# RPi-Display_v10.net
KiCad netlist of a schematic drawn in EAGLE
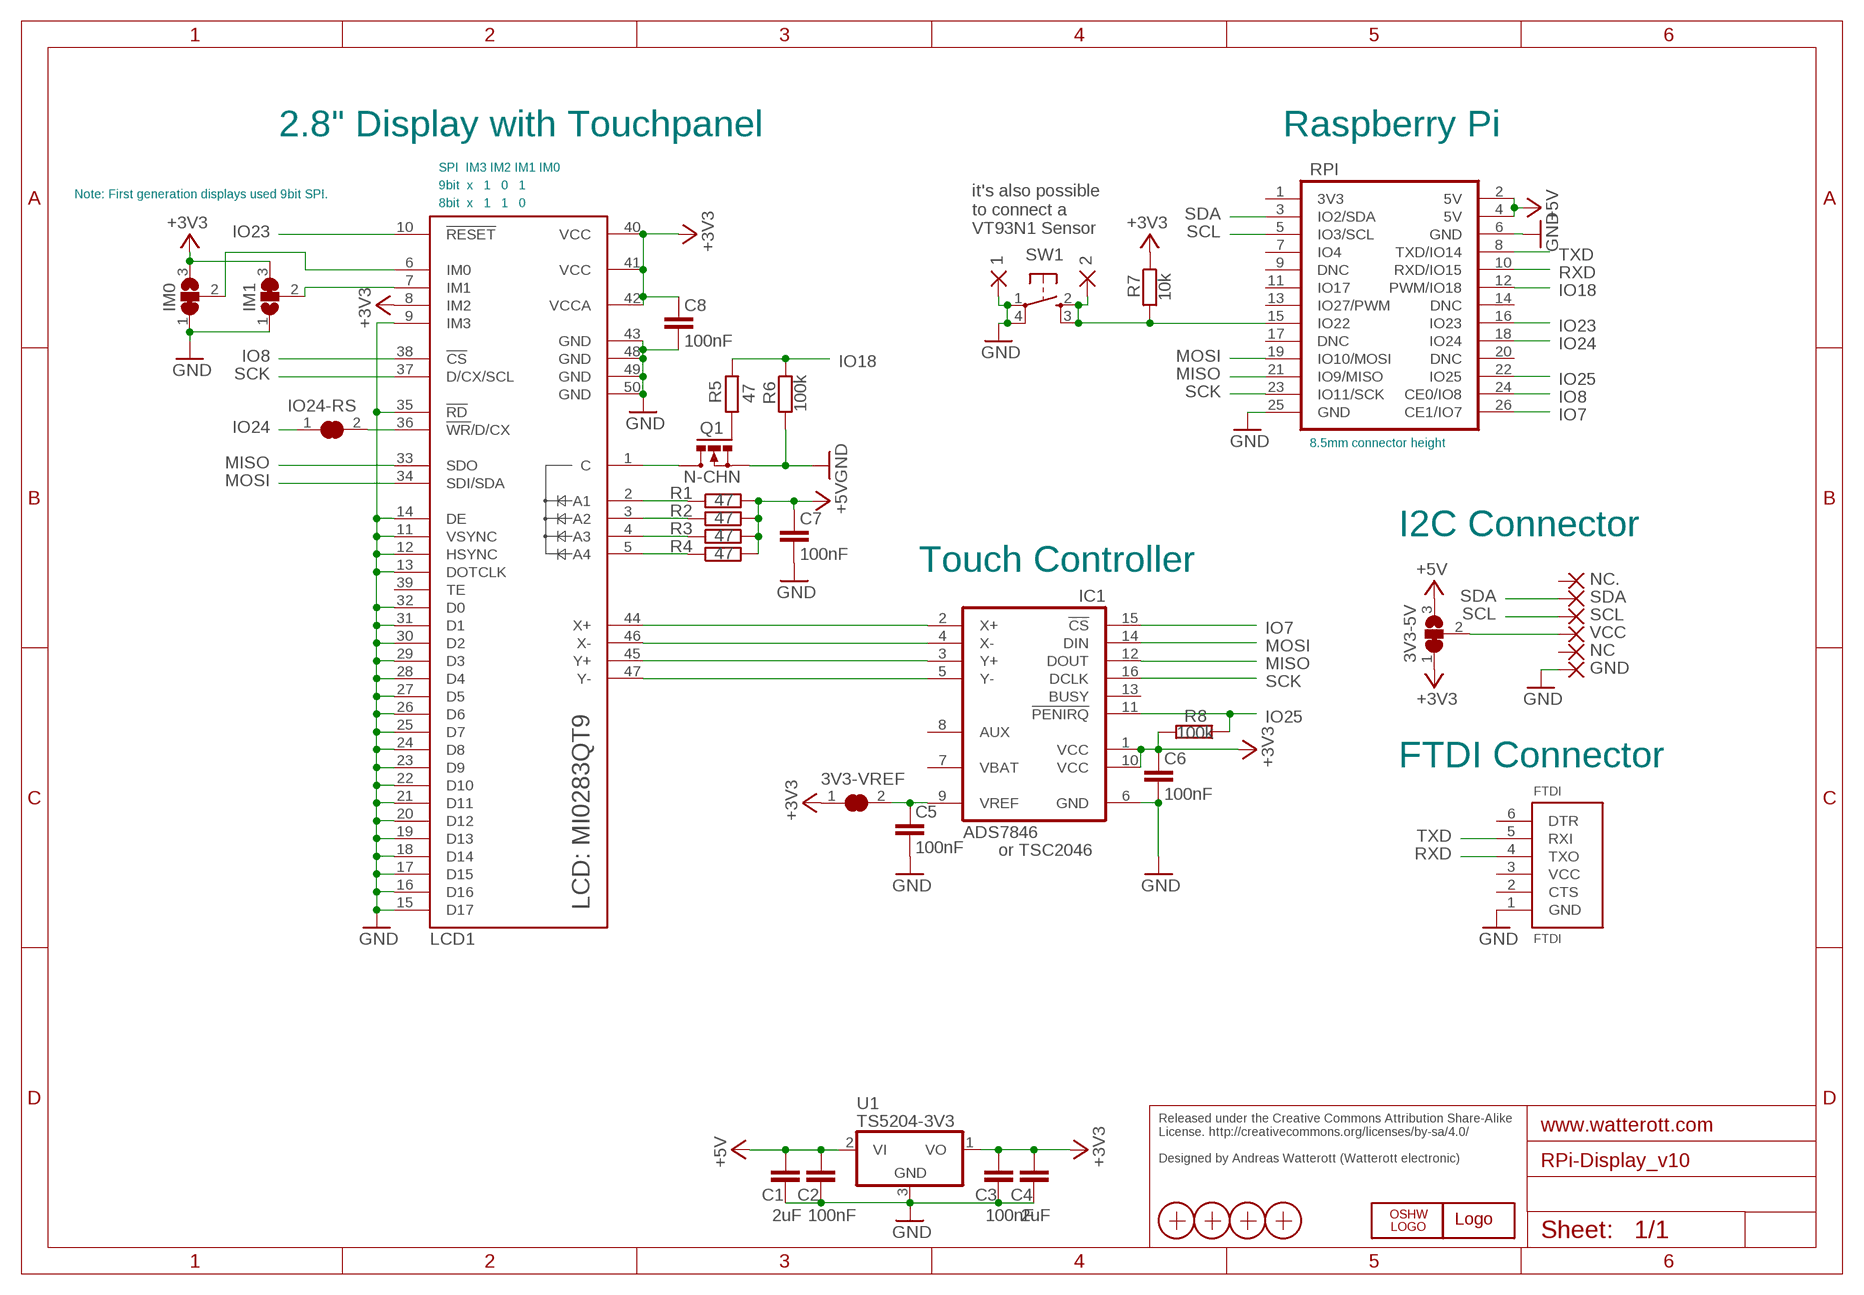
[diagram p0: schematic, sheet 1]

(export (version "E")
  (design (tool "Eeschema 10.0.6"))
  (components
    (comp (ref "1")
      (value "WIREPADSMD1,27-254")
      (footprint "eagle-import:SMD1,27-2,54")
      (libsource (lib "eagle-import") (part "WIREPADSMD1,27-254"))
    )
    (comp (ref "2")
      (value "WIREPADSMD1,27-254")
      (footprint "eagle-import:SMD1,27-2,54")
      (libsource (lib "eagle-import") (part "WIREPADSMD1,27-254"))
    )
    (comp (ref "3V3-5V")
      (value "SJ2W")
      (footprint "eagle-import:SJ_2")
      (libsource (lib "eagle-import") (part "SJ2W"))
    )
    (comp (ref "3V3-VREF")
      (value "SJ")
      (footprint "eagle-import:SJ")
      (libsource (lib "eagle-import") (part "SJ"))
    )
    (comp (ref "C1")
      (value "2uF")
      (footprint "eagle-import:C0603")
      (libsource (lib "eagle-import") (part "C-EUC0603"))
    )
    (comp (ref "C2")
      (value "100nF")
      (footprint "eagle-import:C0603")
      (libsource (lib "eagle-import") (part "C-EUC0603"))
    )
    (comp (ref "C3")
      (value "100nF")
      (footprint "eagle-import:C0603")
      (libsource (lib "eagle-import") (part "C-EUC0603"))
    )
    (comp (ref "C4")
      (value "2uF")
      (footprint "eagle-import:C0603")
      (libsource (lib "eagle-import") (part "C-EUC0603"))
    )
    (comp (ref "C5")
      (value "100nF")
      (footprint "eagle-import:C0603")
      (libsource (lib "eagle-import") (part "C-EUC0603"))
    )
    (comp (ref "C6")
      (value "100nF")
      (footprint "eagle-import:C0603")
      (libsource (lib "eagle-import") (part "C-EUC0603"))
    )
    (comp (ref "C7")
      (value "100nF")
      (footprint "eagle-import:C0603")
      (libsource (lib "eagle-import") (part "C-EUC0603"))
    )
    (comp (ref "C8")
      (value "100nF")
      (footprint "eagle-import:C0603")
      (libsource (lib "eagle-import") (part "C-EUC0603"))
    )
    (comp (ref "FTDI")
      (value "FTDI")
      (footprint "eagle-import:FTDI")
      (libsource (lib "eagle-import") (part "FTDI"))
    )
    (comp (ref "GND")
      (value "WIREPADSMD1,27-254")
      (footprint "eagle-import:SMD1,27-2,54")
      (libsource (lib "eagle-import") (part "WIREPADSMD1,27-254"))
    )
    (comp (ref "IC1")
      (value "ADS7846")
      (footprint "eagle-import:SSOP16")
      (libsource (lib "eagle-import") (part "ADS7846"))
    )
    (comp (ref "IM0")
      (value "SJ2W")
      (footprint "eagle-import:SJ_2")
      (libsource (lib "eagle-import") (part "SJ2W"))
    )
    (comp (ref "IM1")
      (value "SJ2W")
      (footprint "eagle-import:SJ_2")
      (libsource (lib "eagle-import") (part "SJ2W"))
    )
    (comp (ref "IO24-RS")
      (value "SJ")
      (footprint "eagle-import:SJ")
      (libsource (lib "eagle-import") (part "SJ"))
    )
    (comp (ref "LCD1")
      (value "MI0283QT9")
      (footprint "eagle-import:MI0283QT9")
      (libsource (lib "eagle-import") (part "MI0283QT9"))
    )
    (comp (ref "LOGO1")
      (value "OSHW_LOGO_6MILX0150-NT")
      (footprint "eagle-import:OSHW_6X150_NOTEXT")
      (libsource (lib "eagle-import") (part "OSHW_LOGO_6MILX0150-NT"))
    )
    (comp (ref "NC")
      (value "WIREPADSMD1,27-254")
      (footprint "eagle-import:SMD1,27-2,54")
      (libsource (lib "eagle-import") (part "WIREPADSMD1,27-254"))
    )
    (comp (ref "NC.")
      (value "WIREPADSMD1,27-254")
      (footprint "eagle-import:SMD1,27-2,54")
      (libsource (lib "eagle-import") (part "WIREPADSMD1,27-254"))
    )
    (comp (ref "Q1")
      (value "N-CHN")
      (footprint "eagle-import:MICRO3")
      (libsource (lib "eagle-import") (part "IRLML2502"))
    )
    (comp (ref "R1")
      (value "47")
      (footprint "eagle-import:R0603")
      (libsource (lib "eagle-import") (part "R-EU_R0603"))
    )
    (comp (ref "R2")
      (value "47")
      (footprint "eagle-import:R0603")
      (libsource (lib "eagle-import") (part "R-EU_R0603"))
    )
    (comp (ref "R3")
      (value "47")
      (footprint "eagle-import:R0603")
      (libsource (lib "eagle-import") (part "R-EU_R0603"))
    )
    (comp (ref "R4")
      (value "47")
      (footprint "eagle-import:R0603")
      (libsource (lib "eagle-import") (part "R-EU_R0603"))
    )
    (comp (ref "R5")
      (value "47")
      (footprint "eagle-import:R0603")
      (libsource (lib "eagle-import") (part "R-EU_R0603"))
    )
    (comp (ref "R6")
      (value "100k")
      (footprint "eagle-import:R0603")
      (libsource (lib "eagle-import") (part "R-EU_R0603"))
    )
    (comp (ref "R7")
      (value "10k")
      (footprint "eagle-import:R0603")
      (libsource (lib "eagle-import") (part "R-EU_R0603"))
    )
    (comp (ref "R8")
      (value "100k")
      (footprint "eagle-import:R0603")
      (libsource (lib "eagle-import") (part "R-EU_R0603"))
    )
    (comp (ref "RPI")
      (value "RPI")
      (footprint "eagle-import:RPI")
      (libsource (lib "eagle-import") (part "RPI"))
    )
    (comp (ref "SCL")
      (value "WIREPADSMD1,27-254")
      (footprint "eagle-import:SMD1,27-2,54")
      (libsource (lib "eagle-import") (part "WIREPADSMD1,27-254"))
    )
    (comp (ref "SDA")
      (value "WIREPADSMD1,27-254")
      (footprint "eagle-import:SMD1,27-2,54")
      (libsource (lib "eagle-import") (part "WIREPADSMD1,27-254"))
    )
    (comp (ref "SW1")
      (value "SW4S")
      (footprint "eagle-import:SW_SMD4")
      (libsource (lib "eagle-import") (part "SW4S"))
    )
    (comp (ref "U$1")
      (value "WE-LOGO")
      (footprint "eagle-import:WE-LOGO")
      (libsource (lib "eagle-import") (part "WE-LOGOPLACE"))
    )
    (comp (ref "U1")
      (value "TS5204-3V3")
      (footprint "eagle-import:SOT23")
      (libsource (lib "eagle-import") (part "TS5204"))
    )
    (comp (ref "VCC")
      (value "WIREPADSMD1,27-254")
      (footprint "eagle-import:SMD1,27-2,54")
      (libsource (lib "eagle-import") (part "WIREPADSMD1,27-254"))
    )
    (comp (ref "X1")
      (value "PASSER")
      (footprint "eagle-import:PASSER")
      (libsource (lib "eagle-import") (part "PASSER"))
    )
    (comp (ref "X2")
      (value "PASSER")
      (footprint "eagle-import:PASSER")
      (libsource (lib "eagle-import") (part "PASSER"))
    )
    (comp (ref "X3")
      (value "PASSER")
      (footprint "eagle-import:PASSER")
      (libsource (lib "eagle-import") (part "PASSER"))
    )
    (comp (ref "X4")
      (value "PASSER")
      (footprint "eagle-import:PASSER")
      (libsource (lib "eagle-import") (part "PASSER"))
    )
  )
  (nets
    (net (code "1") (name "+3V3") (class "Default")
      (node (ref "3V3-5V") (pin "1") (pinfunction "1_1") (pintype "passive"))
      (node (ref "3V3-VREF") (pin "1") (pinfunction "1_1") (pintype "passive"))
      (node (ref "C3") (pin "1") (pinfunction "1_1") (pintype "passive"))
      (node (ref "C4") (pin "1") (pinfunction "1_1") (pintype "passive"))
      (node (ref "C6") (pin "1") (pinfunction "1_1") (pintype "passive"))
      (node (ref "C8") (pin "1") (pinfunction "1_1") (pintype "passive"))
      (node (ref "IC1") (pin "1") (pinfunction "VCC_1") (pintype "power_in"))
      (node (ref "IC1") (pin "10") (pinfunction "VCC_10") (pintype "power_in"))
      (node (ref "IM0") (pin "3") (pinfunction "3_3") (pintype "passive"))
      (node (ref "IM1") (pin "3") (pinfunction "3_3") (pintype "passive"))
      (node (ref "LCD1") (pin "40") (pinfunction "VCC_40") (pintype "power_in"))
      (node (ref "LCD1") (pin "41") (pinfunction "VCC_41") (pintype "power_in"))
      (node (ref "LCD1") (pin "42") (pinfunction "VCCA_42") (pintype "power_in"))
      (node (ref "LCD1") (pin "8") (pinfunction "IM2_8") (pintype "input"))
      (node (ref "R7") (pin "1") (pinfunction "1_1") (pintype "passive"))
      (node (ref "R8") (pin "2") (pinfunction "2_2") (pintype "passive"))
      (node (ref "U1") (pin "1") (pinfunction "VO_1") (pintype "passive"))
    )
    (net (code "2") (name "+5V") (class "Default")
      (node (ref "3V3-5V") (pin "3") (pinfunction "3_3") (pintype "passive"))
      (node (ref "C1") (pin "1") (pinfunction "1_1") (pintype "passive"))
      (node (ref "C2") (pin "1") (pinfunction "1_1") (pintype "passive"))
      (node (ref "C7") (pin "1") (pinfunction "1_1") (pintype "passive"))
      (node (ref "R1") (pin "2") (pinfunction "2_2") (pintype "passive"))
      (node (ref "R2") (pin "2") (pinfunction "2_2") (pintype "passive"))
      (node (ref "R3") (pin "2") (pinfunction "2_2") (pintype "passive"))
      (node (ref "R4") (pin "2") (pinfunction "2_2") (pintype "passive"))
      (node (ref "RPI") (pin "2") (pinfunction "5V_2") (pintype "passive"))
      (node (ref "RPI") (pin "4") (pinfunction "5V_4") (pintype "passive"))
      (node (ref "U1") (pin "2") (pinfunction "VI_2") (pintype "input"))
    )
    (net (code "3") (name "/IO7") (class "Default")
      (node (ref "IC1") (pin "15") (pinfunction "~{CS}_15") (pintype "input"))
      (node (ref "RPI") (pin "26") (pinfunction "CE1/IO7_26") (pintype "passive"))
    )
    (net (code "4") (name "/IO8") (class "Default")
      (node (ref "LCD1") (pin "38") (pinfunction "~{CS}_38") (pintype "input"))
      (node (ref "RPI") (pin "24") (pinfunction "CE0/IO8_24") (pintype "passive"))
    )
    (net (code "5") (name "/IO18") (class "Default")
      (node (ref "R5") (pin "2") (pinfunction "2_2") (pintype "passive"))
      (node (ref "R6") (pin "1") (pinfunction "1_1") (pintype "passive"))
      (node (ref "RPI") (pin "12") (pinfunction "PWM/IO18_12") (pintype "passive"))
    )
    (net (code "6") (name "/IO23") (class "Default")
      (node (ref "LCD1") (pin "10") (pinfunction "~{RESET}_10") (pintype "input"))
      (node (ref "RPI") (pin "16") (pinfunction "IO23_16") (pintype "passive"))
    )
    (net (code "7") (name "/IO24") (class "Default")
      (node (ref "IO24-RS") (pin "1") (pinfunction "1_1") (pintype "passive"))
      (node (ref "RPI") (pin "18") (pinfunction "IO24_18") (pintype "passive"))
    )
    (net (code "8") (name "/IO25") (class "Default")
      (node (ref "IC1") (pin "11") (pinfunction "~{PENIRQ}_11") (pintype "output"))
      (node (ref "R8") (pin "1") (pinfunction "1_1") (pintype "passive"))
      (node (ref "RPI") (pin "22") (pinfunction "IO25_22") (pintype "passive"))
    )
    (net (code "9") (name "/MISO") (class "Default")
      (node (ref "IC1") (pin "12") (pinfunction "DOUT_12") (pintype "input"))
      (node (ref "LCD1") (pin "33") (pinfunction "SDO_33") (pintype "output"))
      (node (ref "RPI") (pin "21") (pinfunction "IO9/MISO_21") (pintype "passive"))
    )
    (net (code "10") (name "/MOSI") (class "Default")
      (node (ref "IC1") (pin "14") (pinfunction "DIN_14") (pintype "input"))
      (node (ref "LCD1") (pin "34") (pinfunction "SDI/SDA_34") (pintype "input"))
      (node (ref "RPI") (pin "19") (pinfunction "IO10/MOSI_19") (pintype "passive"))
    )
    (net (code "11") (name "/RXD") (class "Default")
      (node (ref "FTDI") (pin "4") (pinfunction "TXO_4") (pintype "bidirectional"))
      (node (ref "RPI") (pin "10") (pinfunction "RXD/IO15_10") (pintype "passive"))
    )
    (net (code "12") (name "/SCK") (class "Default")
      (node (ref "IC1") (pin "16") (pinfunction "DCLK_16") (pintype "output"))
      (node (ref "LCD1") (pin "37") (pinfunction "D/CX/SCL_37") (pintype "input"))
      (node (ref "RPI") (pin "23") (pinfunction "IO11/SCK_23") (pintype "passive"))
    )
    (net (code "13") (name "/SCL") (class "Default")
      (node (ref "RPI") (pin "5") (pinfunction "IO3/SCL_5") (pintype "passive"))
      (node (ref "SCL") (pin "1") (pinfunction "P_1") (pintype "passive"))
    )
    (net (code "14") (name "/SDA") (class "Default")
      (node (ref "RPI") (pin "3") (pinfunction "IO2/SDA_3") (pintype "passive"))
      (node (ref "SDA") (pin "1") (pinfunction "P_1") (pintype "passive"))
    )
    (net (code "15") (name "/TXD") (class "Default")
      (node (ref "FTDI") (pin "5") (pinfunction "RXI_5") (pintype "bidirectional"))
      (node (ref "RPI") (pin "8") (pinfunction "TXD/IO14_8") (pintype "passive"))
    )
    (net (code "16") (name "GND") (class "Default")
      (node (ref "1") (pin "1") (pinfunction "P_1") (pintype "passive"))
      (node (ref "C1") (pin "2") (pinfunction "2_2") (pintype "passive"))
      (node (ref "C2") (pin "2") (pinfunction "2_2") (pintype "passive"))
      (node (ref "C3") (pin "2") (pinfunction "2_2") (pintype "passive"))
      (node (ref "C4") (pin "2") (pinfunction "2_2") (pintype "passive"))
      (node (ref "C5") (pin "2") (pinfunction "2_2") (pintype "passive"))
      (node (ref "C6") (pin "2") (pinfunction "2_2") (pintype "passive"))
      (node (ref "C7") (pin "2") (pinfunction "2_2") (pintype "passive"))
      (node (ref "C8") (pin "2") (pinfunction "2_2") (pintype "passive"))
      (node (ref "FTDI") (pin "1") (pinfunction "GND_1") (pintype "bidirectional"))
      (node (ref "GND") (pin "1") (pinfunction "P_1") (pintype "passive"))
      (node (ref "IC1") (pin "6") (pinfunction "GND_6") (pintype "power_in"))
      (node (ref "IM0") (pin "1") (pinfunction "1_1") (pintype "passive"))
      (node (ref "IM1") (pin "1") (pinfunction "1_1") (pintype "passive"))
      (node (ref "LCD1") (pin "11") (pinfunction "VSYNC_11") (pintype "input"))
      (node (ref "LCD1") (pin "12") (pinfunction "HSYNC_12") (pintype "input"))
      (node (ref "LCD1") (pin "13") (pinfunction "DOTCLK_13") (pintype "input"))
      (node (ref "LCD1") (pin "14") (pinfunction "DE_14") (pintype "input"))
      (node (ref "LCD1") (pin "15") (pinfunction "D17_15") (pintype "input"))
      (node (ref "LCD1") (pin "16") (pinfunction "D16_16") (pintype "input"))
      (node (ref "LCD1") (pin "17") (pinfunction "D15_17") (pintype "input"))
      (node (ref "LCD1") (pin "18") (pinfunction "D14_18") (pintype "input"))
      (node (ref "LCD1") (pin "19") (pinfunction "D13_19") (pintype "input"))
      (node (ref "LCD1") (pin "20") (pinfunction "D12_20") (pintype "input"))
      (node (ref "LCD1") (pin "21") (pinfunction "D11_21") (pintype "input"))
      (node (ref "LCD1") (pin "22") (pinfunction "D10_22") (pintype "input"))
      (node (ref "LCD1") (pin "23") (pinfunction "D9_23") (pintype "input"))
      (node (ref "LCD1") (pin "24") (pinfunction "D8_24") (pintype "input"))
      (node (ref "LCD1") (pin "25") (pinfunction "D7_25") (pintype "input"))
      (node (ref "LCD1") (pin "26") (pinfunction "D6_26") (pintype "input"))
      (node (ref "LCD1") (pin "27") (pinfunction "D5_27") (pintype "input"))
      (node (ref "LCD1") (pin "28") (pinfunction "D4_28") (pintype "input"))
      (node (ref "LCD1") (pin "29") (pinfunction "D3_29") (pintype "input"))
      (node (ref "LCD1") (pin "30") (pinfunction "D2_30") (pintype "input"))
      (node (ref "LCD1") (pin "31") (pinfunction "D1_31") (pintype "input"))
      (node (ref "LCD1") (pin "32") (pinfunction "D0_32") (pintype "input"))
      (node (ref "LCD1") (pin "35") (pinfunction "~{RD}_35") (pintype "input"))
      (node (ref "LCD1") (pin "43") (pinfunction "GND_43") (pintype "power_in"))
      (node (ref "LCD1") (pin "48") (pinfunction "GND_48") (pintype "power_in"))
      (node (ref "LCD1") (pin "49") (pinfunction "GND_49") (pintype "power_in"))
      (node (ref "LCD1") (pin "50") (pinfunction "GND_50") (pintype "power_in"))
      (node (ref "LCD1") (pin "9") (pinfunction "IM3_9") (pintype "input"))
      (node (ref "Q1") (pin "2") (pinfunction "S_2") (pintype "passive"))
      (node (ref "R6") (pin "2") (pinfunction "2_2") (pintype "passive"))
      (node (ref "RPI") (pin "25") (pinfunction "GND_25") (pintype "passive"))
      (node (ref "RPI") (pin "6") (pinfunction "GND_6") (pintype "passive"))
      (node (ref "SW1") (pin "1") (pinfunction "P_1") (pintype "passive"))
      (node (ref "SW1") (pin "4") (pinfunction "P1_4") (pintype "passive"))
      (node (ref "U1") (pin "3") (pinfunction "GND_3") (pintype "passive"))
    )
    (net (code "17") (name "Net-(2-P)") (class "Default")
      (node (ref "2") (pin "1") (pinfunction "P_1") (pintype "passive"))
      (node (ref "R7") (pin "2") (pinfunction "2_2") (pintype "passive"))
      (node (ref "RPI") (pin "15") (pinfunction "IO22_15") (pintype "passive"))
      (node (ref "SW1") (pin "2") (pinfunction "S_2") (pintype "passive"))
      (node (ref "SW1") (pin "3") (pinfunction "S1_3") (pintype "passive"))
    )
    (net (code "18") (name "Net-(IC1-VREF)") (class "Default")
      (node (ref "3V3-VREF") (pin "2") (pinfunction "2_2") (pintype "passive"))
      (node (ref "C5") (pin "1") (pinfunction "1_1") (pintype "passive"))
      (node (ref "IC1") (pin "9") (pinfunction "VREF_9") (pintype "bidirectional"))
    )
    (net (code "19") (name "Net-(IC1-X+)") (class "Default")
      (node (ref "IC1") (pin "2") (pinfunction "X+_2") (pintype "input"))
      (node (ref "LCD1") (pin "44") (pinfunction "X+_44") (pintype "passive"))
    )
    (net (code "20") (name "Net-(IC1-X-)") (class "Default")
      (node (ref "IC1") (pin "4") (pinfunction "X-_4") (pintype "input"))
      (node (ref "LCD1") (pin "46") (pinfunction "X-_46") (pintype "passive"))
    )
    (net (code "21") (name "Net-(IC1-Y+)") (class "Default")
      (node (ref "IC1") (pin "3") (pinfunction "Y+_3") (pintype "input"))
      (node (ref "LCD1") (pin "45") (pinfunction "Y+_45") (pintype "passive"))
    )
    (net (code "22") (name "Net-(IC1-Y-)") (class "Default")
      (node (ref "IC1") (pin "5") (pinfunction "Y-_5") (pintype "input"))
      (node (ref "LCD1") (pin "47") (pinfunction "Y-_47") (pintype "passive"))
    )
    (net (code "23") (name "Net-(LCD1-A1)") (class "Default")
      (node (ref "LCD1") (pin "2") (pinfunction "A1_2") (pintype "power_in"))
      (node (ref "R1") (pin "1") (pinfunction "1_1") (pintype "passive"))
    )
    (net (code "24") (name "Net-(LCD1-A2)") (class "Default")
      (node (ref "LCD1") (pin "3") (pinfunction "A2_3") (pintype "power_in"))
      (node (ref "R2") (pin "1") (pinfunction "1_1") (pintype "passive"))
    )
    (net (code "25") (name "Net-(LCD1-A3)") (class "Default")
      (node (ref "LCD1") (pin "4") (pinfunction "A3_4") (pintype "power_in"))
      (node (ref "R3") (pin "1") (pinfunction "1_1") (pintype "passive"))
    )
    (net (code "26") (name "Net-(LCD1-A4)") (class "Default")
      (node (ref "LCD1") (pin "5") (pinfunction "A4_5") (pintype "power_in"))
      (node (ref "R4") (pin "1") (pinfunction "1_1") (pintype "passive"))
    )
    (net (code "27") (name "Net-(LCD1-C)") (class "Default")
      (node (ref "LCD1") (pin "1") (pinfunction "C_1") (pintype "power_in"))
      (node (ref "Q1") (pin "3") (pinfunction "D_3") (pintype "passive"))
    )
    (net (code "28") (name "Net-(LCD1-IM0)") (class "Default")
      (node (ref "IM0") (pin "2") (pinfunction "2_2") (pintype "passive"))
      (node (ref "LCD1") (pin "6") (pinfunction "IM0_6") (pintype "input"))
    )
    (net (code "29") (name "Net-(LCD1-IM1)") (class "Default")
      (node (ref "IM1") (pin "2") (pinfunction "2_2") (pintype "passive"))
      (node (ref "LCD1") (pin "7") (pinfunction "IM1_7") (pintype "input"))
    )
    (net (code "30") (name "Net-(LCD1-~{WR}{slash}D{slash}CX)") (class "Default")
      (node (ref "IO24-RS") (pin "2") (pinfunction "2_2") (pintype "passive"))
      (node (ref "LCD1") (pin "36") (pinfunction "~{WR}/D/CX_36") (pintype "input"))
    )
    (net (code "31") (name "Net-(Q1-G)") (class "Default")
      (node (ref "Q1") (pin "1") (pinfunction "G_1") (pintype "passive"))
      (node (ref "R5") (pin "1") (pinfunction "1_1") (pintype "passive"))
    )
    (net (code "32") (name "Net-(VCC-P)") (class "Default")
      (node (ref "3V3-5V") (pin "2") (pinfunction "2_2") (pintype "passive"))
      (node (ref "VCC") (pin "1") (pinfunction "P_1") (pintype "passive"))
    )
    (net (code "33") (name "unconnected-(FTDI-CTS-Pad2)") (class "Default")
      (node (ref "FTDI") (pin "2") (pinfunction "CTS_2") (pintype "bidirectional"))
    )
    (net (code "34") (name "unconnected-(FTDI-DTR-Pad6)") (class "Default")
      (node (ref "FTDI") (pin "6") (pinfunction "DTR_6") (pintype "bidirectional"))
    )
    (net (code "35") (name "unconnected-(FTDI-VCC-Pad3)") (class "Default")
      (node (ref "FTDI") (pin "3") (pinfunction "VCC_3") (pintype "bidirectional"))
    )
    (net (code "36") (name "unconnected-(IC1-AUX-Pad8)") (class "Default")
      (node (ref "IC1") (pin "8") (pinfunction "AUX_8") (pintype "input"))
    )
    (net (code "37") (name "unconnected-(IC1-BUSY-Pad13)") (class "Default")
      (node (ref "IC1") (pin "13") (pinfunction "BUSY_13") (pintype "output"))
    )
    (net (code "38") (name "unconnected-(IC1-VBAT-Pad7)") (class "Default")
      (node (ref "IC1") (pin "7") (pinfunction "VBAT_7") (pintype "input"))
    )
    (net (code "39") (name "unconnected-(LCD1-TE-Pad39)") (class "Default")
      (node (ref "LCD1") (pin "39") (pinfunction "TE_39") (pintype "output"))
    )
    (net (code "40") (name "unconnected-(NC-P-Pad1)") (class "Default")
      (node (ref "NC") (pin "1") (pinfunction "P_1") (pintype "passive"))
    )
    (net (code "41") (name "unconnected-(NC.-P-Pad1)") (class "Default")
      (node (ref "NC.") (pin "1") (pinfunction "P_1") (pintype "passive"))
    )
    (net (code "42") (name "unconnected-(RPI-3V3-Pad1)") (class "Default")
      (node (ref "RPI") (pin "1") (pinfunction "3V3_1") (pintype "passive"))
    )
    (net (code "43") (name "unconnected-(RPI-DNC-Pad9)") (class "Default")
      (node (ref "RPI") (pin "9") (pinfunction "DNC_9") (pintype "passive"))
    )
    (net (code "44") (name "unconnected-(RPI-DNC-Pad14)") (class "Default")
      (node (ref "RPI") (pin "14") (pinfunction "DNC_14") (pintype "passive"))
    )
    (net (code "45") (name "unconnected-(RPI-DNC-Pad17)") (class "Default")
      (node (ref "RPI") (pin "17") (pinfunction "DNC_17") (pintype "passive"))
    )
    (net (code "46") (name "unconnected-(RPI-DNC-Pad20)") (class "Default")
      (node (ref "RPI") (pin "20") (pinfunction "DNC_20") (pintype "passive"))
    )
    (net (code "47") (name "unconnected-(RPI-IO4-Pad7)") (class "Default")
      (node (ref "RPI") (pin "7") (pinfunction "IO4_7") (pintype "passive"))
    )
    (net (code "48") (name "unconnected-(RPI-IO17-Pad11)") (class "Default")
      (node (ref "RPI") (pin "11") (pinfunction "IO17_11") (pintype "passive"))
    )
    (net (code "49") (name "unconnected-(RPI-IO27{slash}PWM-Pad13)") (class "Default")
      (node (ref "RPI") (pin "13") (pinfunction "IO27/PWM_13") (pintype "passive"))
    )
  )
)
